# PCB-DISPARRAY4b.net
KiCad netlist of a schematic drawn in EAGLE
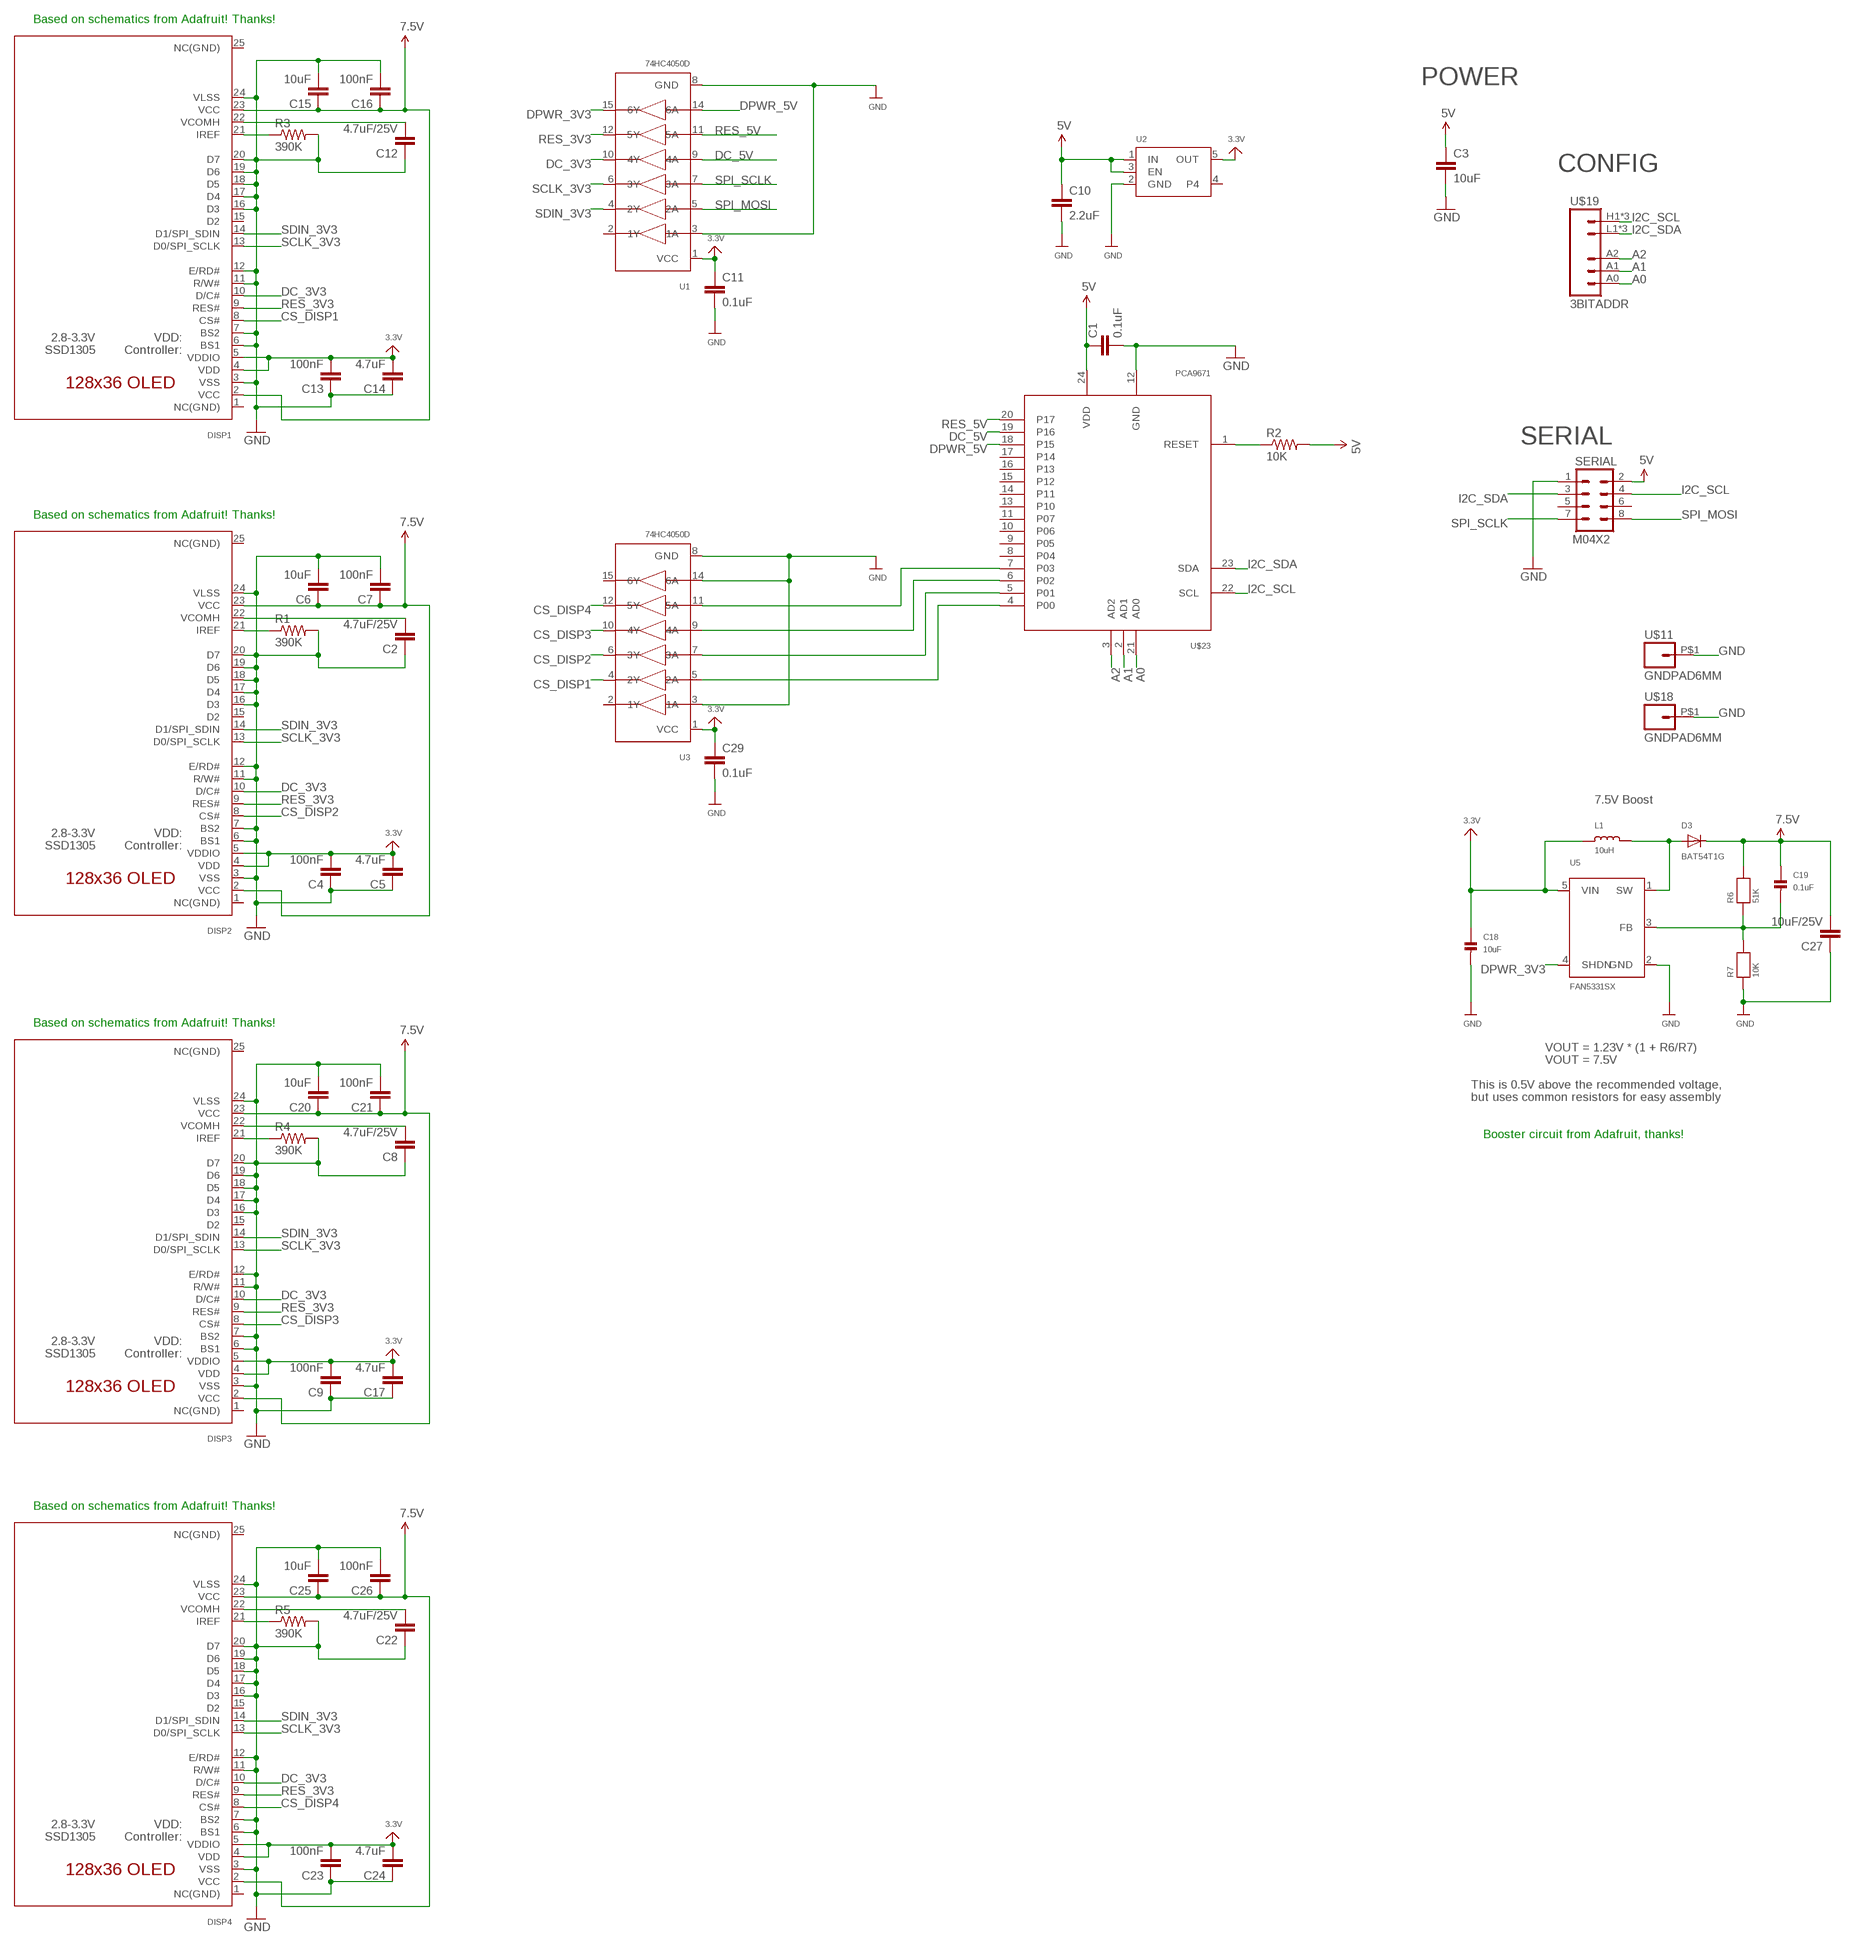
[diagram p0: schematic, sheet 1]

(export (version "E")
  (design (tool "Eeschema 10.0.6"))
  (components
    (comp (ref "C1")
      (value "0.1uF")
      (footprint "eagle-import:0603-CAP")
      (libsource (lib "eagle-import") (part "CAP0603-CAP"))
    )
    (comp (ref "C2")
      (value "4.7uF/25V")
      (footprint "eagle-import:0805")
      (libsource (lib "eagle-import") (part "CAP0805"))
    )
    (comp (ref "C3")
      (value "10uF")
      (footprint "eagle-import:0805")
      (libsource (lib "eagle-import") (part "CAP0805"))
    )
    (comp (ref "C4")
      (value "100nF")
      (footprint "eagle-import:0603-CAP")
      (libsource (lib "eagle-import") (part "CAP0603-CAP"))
    )
    (comp (ref "C5")
      (value "4.7uF")
      (footprint "eagle-import:0603-CAP")
      (libsource (lib "eagle-import") (part "CAP0603-CAP"))
    )
    (comp (ref "C6")
      (value "10uF")
      (footprint "eagle-import:0805")
      (libsource (lib "eagle-import") (part "CAP0805"))
    )
    (comp (ref "C7")
      (value "100nF")
      (footprint "eagle-import:0603-CAP")
      (libsource (lib "eagle-import") (part "CAP0603-CAP"))
    )
    (comp (ref "C8")
      (value "4.7uF/25V")
      (footprint "eagle-import:0805")
      (libsource (lib "eagle-import") (part "CAP0805"))
    )
    (comp (ref "C9")
      (value "100nF")
      (footprint "eagle-import:0603-CAP")
      (libsource (lib "eagle-import") (part "CAP0603-CAP"))
    )
    (comp (ref "C10")
      (value "2.2uF")
      (footprint "eagle-import:0603-CAP")
      (libsource (lib "eagle-import") (part "CAP0603-CAP"))
    )
    (comp (ref "C11")
      (value "0.1uF")
      (footprint "eagle-import:0603-CAP")
      (libsource (lib "eagle-import") (part "CAP0603-CAP"))
    )
    (comp (ref "C12")
      (value "4.7uF/25V")
      (footprint "eagle-import:0805")
      (libsource (lib "eagle-import") (part "CAP0805"))
    )
    (comp (ref "C13")
      (value "100nF")
      (footprint "eagle-import:0603-CAP")
      (libsource (lib "eagle-import") (part "CAP0603-CAP"))
    )
    (comp (ref "C14")
      (value "4.7uF")
      (footprint "eagle-import:0603-CAP")
      (libsource (lib "eagle-import") (part "CAP0603-CAP"))
    )
    (comp (ref "C15")
      (value "10uF")
      (footprint "eagle-import:0805")
      (libsource (lib "eagle-import") (part "CAP0805"))
    )
    (comp (ref "C16")
      (value "100nF")
      (footprint "eagle-import:0603-CAP")
      (libsource (lib "eagle-import") (part "CAP0603-CAP"))
    )
    (comp (ref "C17")
      (value "4.7uF")
      (footprint "eagle-import:0603-CAP")
      (libsource (lib "eagle-import") (part "CAP0603-CAP"))
    )
    (comp (ref "C18")
      (value "10uF")
      (footprint "eagle-import:0805")
      (libsource (lib "eagle-import") (part "CAP_CERAMIC0805"))
    )
    (comp (ref "C19")
      (value "0.1uF")
      (footprint "eagle-import:0603")
      (libsource (lib "eagle-import") (part "CAP_CERAMIC0603"))
    )
    (comp (ref "C20")
      (value "10uF")
      (footprint "eagle-import:0805")
      (libsource (lib "eagle-import") (part "CAP0805"))
    )
    (comp (ref "C21")
      (value "100nF")
      (footprint "eagle-import:0603-CAP")
      (libsource (lib "eagle-import") (part "CAP0603-CAP"))
    )
    (comp (ref "C22")
      (value "4.7uF/25V")
      (footprint "eagle-import:0805")
      (libsource (lib "eagle-import") (part "CAP0805"))
    )
    (comp (ref "C23")
      (value "100nF")
      (footprint "eagle-import:0603-CAP")
      (libsource (lib "eagle-import") (part "CAP0603-CAP"))
    )
    (comp (ref "C24")
      (value "4.7uF")
      (footprint "eagle-import:0603-CAP")
      (libsource (lib "eagle-import") (part "CAP0603-CAP"))
    )
    (comp (ref "C25")
      (value "10uF")
      (footprint "eagle-import:0805")
      (libsource (lib "eagle-import") (part "CAP0805"))
    )
    (comp (ref "C26")
      (value "100nF")
      (footprint "eagle-import:0603-CAP")
      (libsource (lib "eagle-import") (part "CAP0603-CAP"))
    )
    (comp (ref "C27")
      (value "10uF/25V")
      (footprint "eagle-import:0805")
      (libsource (lib "eagle-import") (part "CAP0805"))
    )
    (comp (ref "C29")
      (value "0.1uF")
      (footprint "eagle-import:0603-CAP")
      (libsource (lib "eagle-import") (part "CAP0603-CAP"))
    )
    (comp (ref "D3")
      (value "BAT54T1G")
      (footprint "eagle-import:SOD-123")
      (libsource (lib "eagle-import") (part "DIODESOD-123"))
    )
    (comp (ref "DISP1")
      (value "ER-OLED011-1TOP")
      (footprint "eagle-import:ER-OLED011-1")
      (libsource (lib "eagle-import") (part "ER-OLED011-1TOP"))
    )
    (comp (ref "DISP2")
      (value "ER-OLED011-1TOP")
      (footprint "eagle-import:ER-OLED011-1")
      (libsource (lib "eagle-import") (part "ER-OLED011-1TOP"))
    )
    (comp (ref "DISP3")
      (value "ER-OLED011-1TOP")
      (footprint "eagle-import:ER-OLED011-1")
      (libsource (lib "eagle-import") (part "ER-OLED011-1TOP"))
    )
    (comp (ref "DISP4")
      (value "ER-OLED011-1TOP")
      (footprint "eagle-import:ER-OLED011-1")
      (libsource (lib "eagle-import") (part "ER-OLED011-1TOP"))
    )
    (comp (ref "L1")
      (value "10uH")
      (footprint "eagle-import:INDUCTOR_1007")
      (libsource (lib "eagle-import") (part "INDUCTOR"))
    )
    (comp (ref "R1")
      (value "390K")
      (footprint "eagle-import:0603-RES")
      (libsource (lib "eagle-import") (part "RESISTOR0603-RES"))
    )
    (comp (ref "R2")
      (value "10K")
      (footprint "eagle-import:0603-RES")
      (libsource (lib "eagle-import") (part "RESISTOR0603-RES"))
    )
    (comp (ref "R3")
      (value "390K")
      (footprint "eagle-import:0603-RES")
      (libsource (lib "eagle-import") (part "RESISTOR0603-RES"))
    )
    (comp (ref "R4")
      (value "390K")
      (footprint "eagle-import:0603-RES")
      (libsource (lib "eagle-import") (part "RESISTOR0603-RES"))
    )
    (comp (ref "R5")
      (value "390K")
      (footprint "eagle-import:0603-RES")
      (libsource (lib "eagle-import") (part "RESISTOR0603-RES"))
    )
    (comp (ref "R6")
      (value "51K")
      (footprint "eagle-import:0603")
      (libsource (lib "eagle-import") (part "RESISTOR0603"))
    )
    (comp (ref "R7")
      (value "10K")
      (footprint "eagle-import:0603")
      (libsource (lib "eagle-import") (part "RESISTOR0603"))
    )
    (comp (ref "SERIAL")
      (value "M04X2")
      (footprint "eagle-import:2X4")
      (libsource (lib "eagle-import") (part "M04X2"))
    )
    (comp (ref "U$11")
      (value "GNDPAD6MM")
      (footprint "eagle-import:3.2MMPAD6MM")
      (libsource (lib "eagle-import") (part "GNDPAD6MM"))
    )
    (comp (ref "U$18")
      (value "GNDPAD6MM")
      (footprint "eagle-import:3.2MMPAD6MM")
      (libsource (lib "eagle-import") (part "GNDPAD6MM"))
    )
    (comp (ref "U$19")
      (value "3BITADDR")
      (footprint "eagle-import:3BITADDR")
      (libsource (lib "eagle-import") (part "3BITADDR"))
    )
    (comp (ref "U$23")
      (value "PCA9671")
      (footprint "eagle-import:TSSOP24")
      (libsource (lib "eagle-import") (part "PCA9671"))
    )
    (comp (ref "U1")
      (value "74HC4050D")
      (footprint "eagle-import:TSSOP16")
      (libsource (lib "eagle-import") (part "74HC4050DTSSOP16"))
    )
    (comp (ref "U2")
      (value "VREG_SOT23-5")
      (footprint "eagle-import:SOT23-5")
      (libsource (lib "eagle-import") (part "VREG_SOT23-5"))
    )
    (comp (ref "U3")
      (value "74HC4050D")
      (footprint "eagle-import:TSSOP16")
      (libsource (lib "eagle-import") (part "74HC4050DTSSOP16"))
    )
    (comp (ref "U5")
      (value "FAN5331SX")
      (footprint "eagle-import:SOT23-5")
      (libsource (lib "eagle-import") (part "FAN5331"))
    )
  )
  (nets
    (net (code "1") (name "3.3V") (class "Default")
      (node (ref "C11") (pin "1") (pinfunction "1_1") (pintype "passive"))
      (node (ref "C13") (pin "2") (pinfunction "2_2") (pintype "passive"))
      (node (ref "C14") (pin "2") (pinfunction "2_2") (pintype "passive"))
      (node (ref "C17") (pin "2") (pinfunction "2_2") (pintype "passive"))
      (node (ref "C18") (pin "1") (pinfunction "P$1_1") (pintype "passive"))
      (node (ref "C23") (pin "2") (pinfunction "2_2") (pintype "passive"))
      (node (ref "C24") (pin "2") (pinfunction "2_2") (pintype "passive"))
      (node (ref "C29") (pin "1") (pinfunction "1_1") (pintype "passive"))
      (node (ref "C4") (pin "2") (pinfunction "2_2") (pintype "passive"))
      (node (ref "C5") (pin "2") (pinfunction "2_2") (pintype "passive"))
      (node (ref "C9") (pin "2") (pinfunction "2_2") (pintype "passive"))
      (node (ref "DISP1") (pin "4") (pinfunction "VDD_4") (pintype "power_in"))
      (node (ref "DISP1") (pin "5") (pinfunction "VDDIO_5") (pintype "power_in"))
      (node (ref "DISP2") (pin "4") (pinfunction "VDD_4") (pintype "power_in"))
      (node (ref "DISP2") (pin "5") (pinfunction "VDDIO_5") (pintype "power_in"))
      (node (ref "DISP3") (pin "4") (pinfunction "VDD_4") (pintype "power_in"))
      (node (ref "DISP3") (pin "5") (pinfunction "VDDIO_5") (pintype "power_in"))
      (node (ref "DISP4") (pin "4") (pinfunction "VDD_4") (pintype "power_in"))
      (node (ref "DISP4") (pin "5") (pinfunction "VDDIO_5") (pintype "power_in"))
      (node (ref "L1") (pin "P$1") (pinfunction "1_P$1") (pintype "passive"))
      (node (ref "U1") (pin "1") (pinfunction "VCC_1") (pintype "bidirectional"))
      (node (ref "U2") (pin "5") (pinfunction "OUT_5") (pintype "bidirectional"))
      (node (ref "U3") (pin "1") (pinfunction "VCC_1") (pintype "bidirectional"))
      (node (ref "U5") (pin "5") (pinfunction "VIN_5") (pintype "bidirectional"))
    )
    (net (code "2") (name "5V") (class "Default")
      (node (ref "C1") (pin "1") (pinfunction "1_1") (pintype "passive"))
      (node (ref "C10") (pin "1") (pinfunction "1_1") (pintype "passive"))
      (node (ref "C3") (pin "1") (pinfunction "1_1") (pintype "passive"))
      (node (ref "R2") (pin "2") (pinfunction "2_2") (pintype "passive"))
      (node (ref "SERIAL") (pin "2") (pinfunction "2_2") (pintype "passive"))
      (node (ref "U$23") (pin "24") (pinfunction "VDD_24") (pintype "power_in"))
      (node (ref "U2") (pin "1") (pinfunction "IN_1") (pintype "bidirectional"))
      (node (ref "U2") (pin "3") (pinfunction "EN_3") (pintype "bidirectional"))
    )
    (net (code "3") (name "7.5V") (class "Default")
      (node (ref "C15") (pin "1") (pinfunction "1_1") (pintype "passive"))
      (node (ref "C16") (pin "1") (pinfunction "1_1") (pintype "passive"))
      (node (ref "C19") (pin "1") (pinfunction "P$1_1") (pintype "passive"))
      (node (ref "C20") (pin "1") (pinfunction "1_1") (pintype "passive"))
      (node (ref "C21") (pin "1") (pinfunction "1_1") (pintype "passive"))
      (node (ref "C25") (pin "1") (pinfunction "1_1") (pintype "passive"))
      (node (ref "C26") (pin "1") (pinfunction "1_1") (pintype "passive"))
      (node (ref "C27") (pin "2") (pinfunction "2_2") (pintype "passive"))
      (node (ref "C6") (pin "1") (pinfunction "1_1") (pintype "passive"))
      (node (ref "C7") (pin "1") (pinfunction "1_1") (pintype "passive"))
      (node (ref "D3") (pin "C") (pinfunction "C_C") (pintype "passive"))
      (node (ref "DISP1") (pin "2") (pinfunction "VCC_2") (pintype "power_in"))
      (node (ref "DISP1") (pin "23") (pinfunction "VCC_23") (pintype "power_in"))
      (node (ref "DISP2") (pin "2") (pinfunction "VCC_2") (pintype "power_in"))
      (node (ref "DISP2") (pin "23") (pinfunction "VCC_23") (pintype "power_in"))
      (node (ref "DISP3") (pin "2") (pinfunction "VCC_2") (pintype "power_in"))
      (node (ref "DISP3") (pin "23") (pinfunction "VCC_23") (pintype "power_in"))
      (node (ref "DISP4") (pin "2") (pinfunction "VCC_2") (pintype "power_in"))
      (node (ref "DISP4") (pin "23") (pinfunction "VCC_23") (pintype "power_in"))
      (node (ref "R6") (pin "2") (pinfunction "2_2") (pintype "passive"))
    )
    (net (code "4") (name "A0") (class "Default")
      (node (ref "U$19") (pin "A0") (pinfunction "A0_A0") (pintype "passive"))
      (node (ref "U$23") (pin "21") (pinfunction "AD0_21") (pintype "input"))
    )
    (net (code "5") (name "A1") (class "Default")
      (node (ref "U$19") (pin "A1") (pinfunction "A1_A1") (pintype "passive"))
      (node (ref "U$23") (pin "2") (pinfunction "AD1_2") (pintype "input"))
    )
    (net (code "6") (name "A2") (class "Default")
      (node (ref "U$19") (pin "A2") (pinfunction "A2_A2") (pintype "passive"))
      (node (ref "U$23") (pin "3") (pinfunction "AD2_3") (pintype "input"))
    )
    (net (code "7") (name "CS_DISP1") (class "Default")
      (node (ref "DISP1") (pin "8") (pinfunction "CS#_8") (pintype "input"))
      (node (ref "U3") (pin "4") (pinfunction "2Y_4") (pintype "bidirectional"))
    )
    (net (code "8") (name "CS_DISP2") (class "Default")
      (node (ref "DISP2") (pin "8") (pinfunction "CS#_8") (pintype "input"))
      (node (ref "U3") (pin "6") (pinfunction "3Y_6") (pintype "bidirectional"))
    )
    (net (code "9") (name "CS_DISP3") (class "Default")
      (node (ref "DISP3") (pin "8") (pinfunction "CS#_8") (pintype "input"))
      (node (ref "U3") (pin "10") (pinfunction "4Y_10") (pintype "bidirectional"))
    )
    (net (code "10") (name "CS_DISP4") (class "Default")
      (node (ref "DISP4") (pin "8") (pinfunction "CS#_8") (pintype "input"))
      (node (ref "U3") (pin "12") (pinfunction "5Y_12") (pintype "bidirectional"))
    )
    (net (code "11") (name "DC_3V3") (class "Default")
      (node (ref "DISP1") (pin "10") (pinfunction "D/C#_10") (pintype "input"))
      (node (ref "DISP2") (pin "10") (pinfunction "D/C#_10") (pintype "input"))
      (node (ref "DISP3") (pin "10") (pinfunction "D/C#_10") (pintype "input"))
      (node (ref "DISP4") (pin "10") (pinfunction "D/C#_10") (pintype "input"))
      (node (ref "U1") (pin "10") (pinfunction "4Y_10") (pintype "bidirectional"))
    )
    (net (code "12") (name "DC_5V") (class "Default")
      (node (ref "U$23") (pin "19") (pinfunction "P16_19") (pintype "output"))
      (node (ref "U1") (pin "9") (pinfunction "4A_9") (pintype "bidirectional"))
    )
    (net (code "13") (name "DPWR_3V3") (class "Default")
      (node (ref "U1") (pin "15") (pinfunction "6Y_15") (pintype "bidirectional"))
      (node (ref "U5") (pin "4") (pinfunction "SHDN_4") (pintype "bidirectional"))
    )
    (net (code "14") (name "DPWR_5V") (class "Default")
      (node (ref "U$23") (pin "18") (pinfunction "P15_18") (pintype "output"))
      (node (ref "U1") (pin "14") (pinfunction "6A_14") (pintype "bidirectional"))
    )
    (net (code "15") (name "GND") (class "Default")
      (node (ref "C1") (pin "2") (pinfunction "2_2") (pintype "passive"))
      (node (ref "C10") (pin "2") (pinfunction "2_2") (pintype "passive"))
      (node (ref "C11") (pin "2") (pinfunction "2_2") (pintype "passive"))
      (node (ref "C12") (pin "1") (pinfunction "1_1") (pintype "passive"))
      (node (ref "C13") (pin "1") (pinfunction "1_1") (pintype "passive"))
      (node (ref "C14") (pin "1") (pinfunction "1_1") (pintype "passive"))
      (node (ref "C15") (pin "2") (pinfunction "2_2") (pintype "passive"))
      (node (ref "C16") (pin "2") (pinfunction "2_2") (pintype "passive"))
      (node (ref "C17") (pin "1") (pinfunction "1_1") (pintype "passive"))
      (node (ref "C18") (pin "2") (pinfunction "P$2_2") (pintype "passive"))
      (node (ref "C2") (pin "1") (pinfunction "1_1") (pintype "passive"))
      (node (ref "C20") (pin "2") (pinfunction "2_2") (pintype "passive"))
      (node (ref "C21") (pin "2") (pinfunction "2_2") (pintype "passive"))
      (node (ref "C22") (pin "1") (pinfunction "1_1") (pintype "passive"))
      (node (ref "C23") (pin "1") (pinfunction "1_1") (pintype "passive"))
      (node (ref "C24") (pin "1") (pinfunction "1_1") (pintype "passive"))
      (node (ref "C25") (pin "2") (pinfunction "2_2") (pintype "passive"))
      (node (ref "C26") (pin "2") (pinfunction "2_2") (pintype "passive"))
      (node (ref "C27") (pin "1") (pinfunction "1_1") (pintype "passive"))
      (node (ref "C29") (pin "2") (pinfunction "2_2") (pintype "passive"))
      (node (ref "C3") (pin "2") (pinfunction "2_2") (pintype "passive"))
      (node (ref "C4") (pin "1") (pinfunction "1_1") (pintype "passive"))
      (node (ref "C5") (pin "1") (pinfunction "1_1") (pintype "passive"))
      (node (ref "C6") (pin "2") (pinfunction "2_2") (pintype "passive"))
      (node (ref "C7") (pin "2") (pinfunction "2_2") (pintype "passive"))
      (node (ref "C8") (pin "1") (pinfunction "1_1") (pintype "passive"))
      (node (ref "C9") (pin "1") (pinfunction "1_1") (pintype "passive"))
      (node (ref "DISP1") (pin "11") (pinfunction "R/W#_11") (pintype "input"))
      (node (ref "DISP1") (pin "12") (pinfunction "E/RD#_12") (pintype "input"))
      (node (ref "DISP1") (pin "16") (pinfunction "D3_16") (pintype "bidirectional"))
      (node (ref "DISP1") (pin "17") (pinfunction "D4_17") (pintype "bidirectional"))
      (node (ref "DISP1") (pin "18") (pinfunction "D5_18") (pintype "bidirectional"))
      (node (ref "DISP1") (pin "19") (pinfunction "D6_19") (pintype "bidirectional"))
      (node (ref "DISP1") (pin "20") (pinfunction "D7_20") (pintype "bidirectional"))
      (node (ref "DISP1") (pin "24") (pinfunction "VLSS_24") (pintype "power_in"))
      (node (ref "DISP1") (pin "3") (pinfunction "VSS_3") (pintype "power_in"))
      (node (ref "DISP1") (pin "6") (pinfunction "BS1_6") (pintype "input"))
      (node (ref "DISP1") (pin "7") (pinfunction "BS2_7") (pintype "input"))
      (node (ref "DISP2") (pin "11") (pinfunction "R/W#_11") (pintype "input"))
      (node (ref "DISP2") (pin "12") (pinfunction "E/RD#_12") (pintype "input"))
      (node (ref "DISP2") (pin "16") (pinfunction "D3_16") (pintype "bidirectional"))
      (node (ref "DISP2") (pin "17") (pinfunction "D4_17") (pintype "bidirectional"))
      (node (ref "DISP2") (pin "18") (pinfunction "D5_18") (pintype "bidirectional"))
      (node (ref "DISP2") (pin "19") (pinfunction "D6_19") (pintype "bidirectional"))
      (node (ref "DISP2") (pin "20") (pinfunction "D7_20") (pintype "bidirectional"))
      (node (ref "DISP2") (pin "24") (pinfunction "VLSS_24") (pintype "power_in"))
      (node (ref "DISP2") (pin "3") (pinfunction "VSS_3") (pintype "power_in"))
      (node (ref "DISP2") (pin "6") (pinfunction "BS1_6") (pintype "input"))
      (node (ref "DISP2") (pin "7") (pinfunction "BS2_7") (pintype "input"))
      (node (ref "DISP3") (pin "11") (pinfunction "R/W#_11") (pintype "input"))
      (node (ref "DISP3") (pin "12") (pinfunction "E/RD#_12") (pintype "input"))
      (node (ref "DISP3") (pin "16") (pinfunction "D3_16") (pintype "bidirectional"))
      (node (ref "DISP3") (pin "17") (pinfunction "D4_17") (pintype "bidirectional"))
      (node (ref "DISP3") (pin "18") (pinfunction "D5_18") (pintype "bidirectional"))
      (node (ref "DISP3") (pin "19") (pinfunction "D6_19") (pintype "bidirectional"))
      (node (ref "DISP3") (pin "20") (pinfunction "D7_20") (pintype "bidirectional"))
      (node (ref "DISP3") (pin "24") (pinfunction "VLSS_24") (pintype "power_in"))
      (node (ref "DISP3") (pin "3") (pinfunction "VSS_3") (pintype "power_in"))
      (node (ref "DISP3") (pin "6") (pinfunction "BS1_6") (pintype "input"))
      (node (ref "DISP3") (pin "7") (pinfunction "BS2_7") (pintype "input"))
      (node (ref "DISP4") (pin "11") (pinfunction "R/W#_11") (pintype "input"))
      (node (ref "DISP4") (pin "12") (pinfunction "E/RD#_12") (pintype "input"))
      (node (ref "DISP4") (pin "16") (pinfunction "D3_16") (pintype "bidirectional"))
      (node (ref "DISP4") (pin "17") (pinfunction "D4_17") (pintype "bidirectional"))
      (node (ref "DISP4") (pin "18") (pinfunction "D5_18") (pintype "bidirectional"))
      (node (ref "DISP4") (pin "19") (pinfunction "D6_19") (pintype "bidirectional"))
      (node (ref "DISP4") (pin "20") (pinfunction "D7_20") (pintype "bidirectional"))
      (node (ref "DISP4") (pin "24") (pinfunction "VLSS_24") (pintype "power_in"))
      (node (ref "DISP4") (pin "3") (pinfunction "VSS_3") (pintype "power_in"))
      (node (ref "DISP4") (pin "6") (pinfunction "BS1_6") (pintype "input"))
      (node (ref "DISP4") (pin "7") (pinfunction "BS2_7") (pintype "input"))
      (node (ref "R1") (pin "2") (pinfunction "2_2") (pintype "passive"))
      (node (ref "R3") (pin "2") (pinfunction "2_2") (pintype "passive"))
      (node (ref "R4") (pin "2") (pinfunction "2_2") (pintype "passive"))
      (node (ref "R5") (pin "2") (pinfunction "2_2") (pintype "passive"))
      (node (ref "R7") (pin "1") (pinfunction "1_1") (pintype "passive"))
      (node (ref "SERIAL") (pin "1") (pinfunction "1_1") (pintype "passive"))
      (node (ref "U$11") (pin "P$1") (pinfunction "1_P$1") (pintype "passive"))
      (node (ref "U$18") (pin "P$1") (pinfunction "1_P$1") (pintype "passive"))
      (node (ref "U$23") (pin "12") (pinfunction "GND_12") (pintype "power_in"))
      (node (ref "U1") (pin "3") (pinfunction "1A_3") (pintype "bidirectional"))
      (node (ref "U1") (pin "8") (pinfunction "GND_8") (pintype "bidirectional"))
      (node (ref "U2") (pin "2") (pinfunction "GND_2") (pintype "bidirectional"))
      (node (ref "U3") (pin "14") (pinfunction "6A_14") (pintype "bidirectional"))
      (node (ref "U3") (pin "3") (pinfunction "1A_3") (pintype "bidirectional"))
      (node (ref "U3") (pin "8") (pinfunction "GND_8") (pintype "bidirectional"))
      (node (ref "U5") (pin "2") (pinfunction "GND_2") (pintype "bidirectional"))
    )
    (net (code "16") (name "I2C_SCL") (class "Default")
      (node (ref "SERIAL") (pin "4") (pinfunction "4_4") (pintype "passive"))
      (node (ref "U$19") (pin "H1") (pinfunction "VCC_H1") (pintype "passive"))
      (node (ref "U$19") (pin "H2") (pinfunction "VCC_H2") (pintype "passive"))
      (node (ref "U$19") (pin "H3") (pinfunction "VCC_H3") (pintype "passive"))
      (node (ref "U$23") (pin "22") (pinfunction "SCL_22") (pintype "input"))
    )
    (net (code "17") (name "I2C_SDA") (class "Default")
      (node (ref "SERIAL") (pin "3") (pinfunction "3_3") (pintype "passive"))
      (node (ref "U$19") (pin "L1") (pinfunction "GND_L1") (pintype "passive"))
      (node (ref "U$19") (pin "L2") (pinfunction "GND_L2") (pintype "passive"))
      (node (ref "U$19") (pin "L3") (pinfunction "GND_L3") (pintype "passive"))
      (node (ref "U$23") (pin "23") (pinfunction "SDA_23") (pintype "input"))
    )
    (net (code "18") (name "Net-(C19-P$2)") (class "Default")
      (node (ref "C19") (pin "2") (pinfunction "P$2_2") (pintype "passive"))
      (node (ref "R6") (pin "1") (pinfunction "1_1") (pintype "passive"))
      (node (ref "R7") (pin "2") (pinfunction "2_2") (pintype "passive"))
      (node (ref "U5") (pin "3") (pinfunction "FB_3") (pintype "bidirectional"))
    )
    (net (code "19") (name "Net-(DISP1-IREF)") (class "Default")
      (node (ref "DISP1") (pin "21") (pinfunction "IREF_21") (pintype "input"))
      (node (ref "R3") (pin "1") (pinfunction "1_1") (pintype "passive"))
    )
    (net (code "20") (name "Net-(DISP1-VCOMH)") (class "Default")
      (node (ref "C12") (pin "2") (pinfunction "2_2") (pintype "passive"))
      (node (ref "DISP1") (pin "22") (pinfunction "VCOMH_22") (pintype "output"))
    )
    (net (code "21") (name "Net-(DISP2-IREF)") (class "Default")
      (node (ref "DISP2") (pin "21") (pinfunction "IREF_21") (pintype "input"))
      (node (ref "R1") (pin "1") (pinfunction "1_1") (pintype "passive"))
    )
    (net (code "22") (name "Net-(DISP2-VCOMH)") (class "Default")
      (node (ref "C2") (pin "2") (pinfunction "2_2") (pintype "passive"))
      (node (ref "DISP2") (pin "22") (pinfunction "VCOMH_22") (pintype "output"))
    )
    (net (code "23") (name "Net-(DISP3-IREF)") (class "Default")
      (node (ref "DISP3") (pin "21") (pinfunction "IREF_21") (pintype "input"))
      (node (ref "R4") (pin "1") (pinfunction "1_1") (pintype "passive"))
    )
    (net (code "24") (name "Net-(DISP3-VCOMH)") (class "Default")
      (node (ref "C8") (pin "2") (pinfunction "2_2") (pintype "passive"))
      (node (ref "DISP3") (pin "22") (pinfunction "VCOMH_22") (pintype "output"))
    )
    (net (code "25") (name "Net-(DISP4-IREF)") (class "Default")
      (node (ref "DISP4") (pin "21") (pinfunction "IREF_21") (pintype "input"))
      (node (ref "R5") (pin "1") (pinfunction "1_1") (pintype "passive"))
    )
    (net (code "26") (name "Net-(DISP4-VCOMH)") (class "Default")
      (node (ref "C22") (pin "2") (pinfunction "2_2") (pintype "passive"))
      (node (ref "DISP4") (pin "22") (pinfunction "VCOMH_22") (pintype "output"))
    )
    (net (code "27") (name "Net-(L1-2)") (class "Default")
      (node (ref "D3") (pin "A") (pinfunction "A_A") (pintype "passive"))
      (node (ref "L1") (pin "P$2") (pinfunction "2_P$2") (pintype "passive"))
      (node (ref "U5") (pin "1") (pinfunction "SW_1") (pintype "bidirectional"))
    )
    (net (code "28") (name "Net-(U$23-P00)") (class "Default")
      (node (ref "U$23") (pin "4") (pinfunction "P00_4") (pintype "output"))
      (node (ref "U3") (pin "5") (pinfunction "2A_5") (pintype "bidirectional"))
    )
    (net (code "29") (name "Net-(U$23-P01)") (class "Default")
      (node (ref "U$23") (pin "5") (pinfunction "P01_5") (pintype "output"))
      (node (ref "U3") (pin "7") (pinfunction "3A_7") (pintype "bidirectional"))
    )
    (net (code "30") (name "Net-(U$23-P02)") (class "Default")
      (node (ref "U$23") (pin "6") (pinfunction "P02_6") (pintype "output"))
      (node (ref "U3") (pin "9") (pinfunction "4A_9") (pintype "bidirectional"))
    )
    (net (code "31") (name "Net-(U$23-P03)") (class "Default")
      (node (ref "U$23") (pin "7") (pinfunction "P03_7") (pintype "output"))
      (node (ref "U3") (pin "11") (pinfunction "5A_11") (pintype "bidirectional"))
    )
    (net (code "32") (name "Net-(U$23-RESET)") (class "Default")
      (node (ref "R2") (pin "1") (pinfunction "1_1") (pintype "passive"))
      (node (ref "U$23") (pin "1") (pinfunction "RESET_1") (pintype "input"))
    )
    (net (code "33") (name "RES_3V3") (class "Default")
      (node (ref "DISP1") (pin "9") (pinfunction "RES#_9") (pintype "input"))
      (node (ref "DISP2") (pin "9") (pinfunction "RES#_9") (pintype "input"))
      (node (ref "DISP3") (pin "9") (pinfunction "RES#_9") (pintype "input"))
      (node (ref "DISP4") (pin "9") (pinfunction "RES#_9") (pintype "input"))
      (node (ref "U1") (pin "12") (pinfunction "5Y_12") (pintype "bidirectional"))
    )
    (net (code "34") (name "RES_5V") (class "Default")
      (node (ref "U$23") (pin "20") (pinfunction "P17_20") (pintype "output"))
      (node (ref "U1") (pin "11") (pinfunction "5A_11") (pintype "bidirectional"))
    )
    (net (code "35") (name "SCLK_3V3") (class "Default")
      (node (ref "DISP1") (pin "13") (pinfunction "D0/SPI_SCLK_13") (pintype "bidirectional"))
      (node (ref "DISP2") (pin "13") (pinfunction "D0/SPI_SCLK_13") (pintype "bidirectional"))
      (node (ref "DISP3") (pin "13") (pinfunction "D0/SPI_SCLK_13") (pintype "bidirectional"))
      (node (ref "DISP4") (pin "13") (pinfunction "D0/SPI_SCLK_13") (pintype "bidirectional"))
      (node (ref "U1") (pin "6") (pinfunction "3Y_6") (pintype "bidirectional"))
    )
    (net (code "36") (name "SDIN_3V3") (class "Default")
      (node (ref "DISP1") (pin "14") (pinfunction "D1/SPI_SDIN_14") (pintype "bidirectional"))
      (node (ref "DISP2") (pin "14") (pinfunction "D1/SPI_SDIN_14") (pintype "bidirectional"))
      (node (ref "DISP3") (pin "14") (pinfunction "D1/SPI_SDIN_14") (pintype "bidirectional"))
      (node (ref "DISP4") (pin "14") (pinfunction "D1/SPI_SDIN_14") (pintype "bidirectional"))
      (node (ref "U1") (pin "4") (pinfunction "2Y_4") (pintype "bidirectional"))
    )
    (net (code "37") (name "SPI_MOSI") (class "Default")
      (node (ref "SERIAL") (pin "8") (pinfunction "8_8") (pintype "passive"))
      (node (ref "U1") (pin "5") (pinfunction "2A_5") (pintype "bidirectional"))
    )
    (net (code "38") (name "SPI_SCLK") (class "Default")
      (node (ref "SERIAL") (pin "7") (pinfunction "7_7") (pintype "passive"))
      (node (ref "U1") (pin "7") (pinfunction "3A_7") (pintype "bidirectional"))
    )
    (net (code "39") (name "unconnected-(DISP1-D2-Pad15)") (class "Default")
      (node (ref "DISP1") (pin "15") (pinfunction "D2_15") (pintype "bidirectional"))
    )
    (net (code "40") (name "unconnected-(DISP1-NC(GND)-Pad1)") (class "Default")
      (node (ref "DISP1") (pin "1") (pinfunction "NC(GND)_1") (pintype "input"))
    )
    (net (code "41") (name "unconnected-(DISP1-NC(GND)-Pad25)") (class "Default")
      (node (ref "DISP1") (pin "25") (pinfunction "NC(GND)_25") (pintype "input"))
    )
    (net (code "42") (name "unconnected-(DISP2-D2-Pad15)") (class "Default")
      (node (ref "DISP2") (pin "15") (pinfunction "D2_15") (pintype "bidirectional"))
    )
    (net (code "43") (name "unconnected-(DISP2-NC(GND)-Pad1)") (class "Default")
      (node (ref "DISP2") (pin "1") (pinfunction "NC(GND)_1") (pintype "input"))
    )
    (net (code "44") (name "unconnected-(DISP2-NC(GND)-Pad25)") (class "Default")
      (node (ref "DISP2") (pin "25") (pinfunction "NC(GND)_25") (pintype "input"))
    )
    (net (code "45") (name "unconnected-(DISP3-D2-Pad15)") (class "Default")
      (node (ref "DISP3") (pin "15") (pinfunction "D2_15") (pintype "bidirectional"))
    )
    (net (code "46") (name "unconnected-(DISP3-NC(GND)-Pad1)") (class "Default")
      (node (ref "DISP3") (pin "1") (pinfunction "NC(GND)_1") (pintype "input"))
    )
    (net (code "47") (name "unconnected-(DISP3-NC(GND)-Pad25)") (class "Default")
      (node (ref "DISP3") (pin "25") (pinfunction "NC(GND)_25") (pintype "input"))
    )
    (net (code "48") (name "unconnected-(DISP4-D2-Pad15)") (class "Default")
      (node (ref "DISP4") (pin "15") (pinfunction "D2_15") (pintype "bidirectional"))
    )
    (net (code "49") (name "unconnected-(DISP4-NC(GND)-Pad1)") (class "Default")
      (node (ref "DISP4") (pin "1") (pinfunction "NC(GND)_1") (pintype "input"))
    )
    (net (code "50") (name "unconnected-(DISP4-NC(GND)-Pad25)") (class "Default")
      (node (ref "DISP4") (pin "25") (pinfunction "NC(GND)_25") (pintype "input"))
    )
    (net (code "51") (name "unconnected-(SERIAL-Pad5)") (class "Default")
      (node (ref "SERIAL") (pin "5") (pinfunction "5_5") (pintype "passive"))
    )
    (net (code "52") (name "unconnected-(SERIAL-Pad6)") (class "Default")
      (node (ref "SERIAL") (pin "6") (pinfunction "6_6") (pintype "passive"))
    )
    (net (code "53") (name "unconnected-(U$23-P04-Pad8)") (class "Default")
      (node (ref "U$23") (pin "8") (pinfunction "P04_8") (pintype "output"))
    )
    (net (code "54") (name "unconnected-(U$23-P05-Pad9)") (class "Default")
      (node (ref "U$23") (pin "9") (pinfunction "P05_9") (pintype "output"))
    )
    (net (code "55") (name "unconnected-(U$23-P06-Pad10)") (class "Default")
      (node (ref "U$23") (pin "10") (pinfunction "P06_10") (pintype "output"))
    )
    (net (code "56") (name "unconnected-(U$23-P07-Pad11)") (class "Default")
      (node (ref "U$23") (pin "11") (pinfunction "P07_11") (pintype "output"))
    )
    (net (code "57") (name "unconnected-(U$23-P10-Pad13)") (class "Default")
      (node (ref "U$23") (pin "13") (pinfunction "P10_13") (pintype "output"))
    )
    (net (code "58") (name "unconnected-(U$23-P11-Pad14)") (class "Default")
      (node (ref "U$23") (pin "14") (pinfunction "P11_14") (pintype "output"))
    )
    (net (code "59") (name "unconnected-(U$23-P12-Pad15)") (class "Default")
      (node (ref "U$23") (pin "15") (pinfunction "P12_15") (pintype "output"))
    )
    (net (code "60") (name "unconnected-(U$23-P13-Pad16)") (class "Default")
      (node (ref "U$23") (pin "16") (pinfunction "P13_16") (pintype "output"))
    )
    (net (code "61") (name "unconnected-(U$23-P14-Pad17)") (class "Default")
      (node (ref "U$23") (pin "17") (pinfunction "P14_17") (pintype "output"))
    )
    (net (code "62") (name "unconnected-(U1-1Y-Pad2)") (class "Default")
      (node (ref "U1") (pin "2") (pinfunction "1Y_2") (pintype "bidirectional"))
    )
    (net (code "63") (name "unconnected-(U2-P4-Pad4)") (class "Default")
      (node (ref "U2") (pin "4") (pinfunction "P4_4") (pintype "bidirectional"))
    )
    (net (code "64") (name "unconnected-(U3-1Y-Pad2)") (class "Default")
      (node (ref "U3") (pin "2") (pinfunction "1Y_2") (pintype "bidirectional"))
    )
    (net (code "65") (name "unconnected-(U3-6Y-Pad15)") (class "Default")
      (node (ref "U3") (pin "15") (pinfunction "6Y_15") (pintype "bidirectional"))
    )
  )
)
